# DSO_IO.net
KiCad netlist of a schematic drawn in Altium Designer
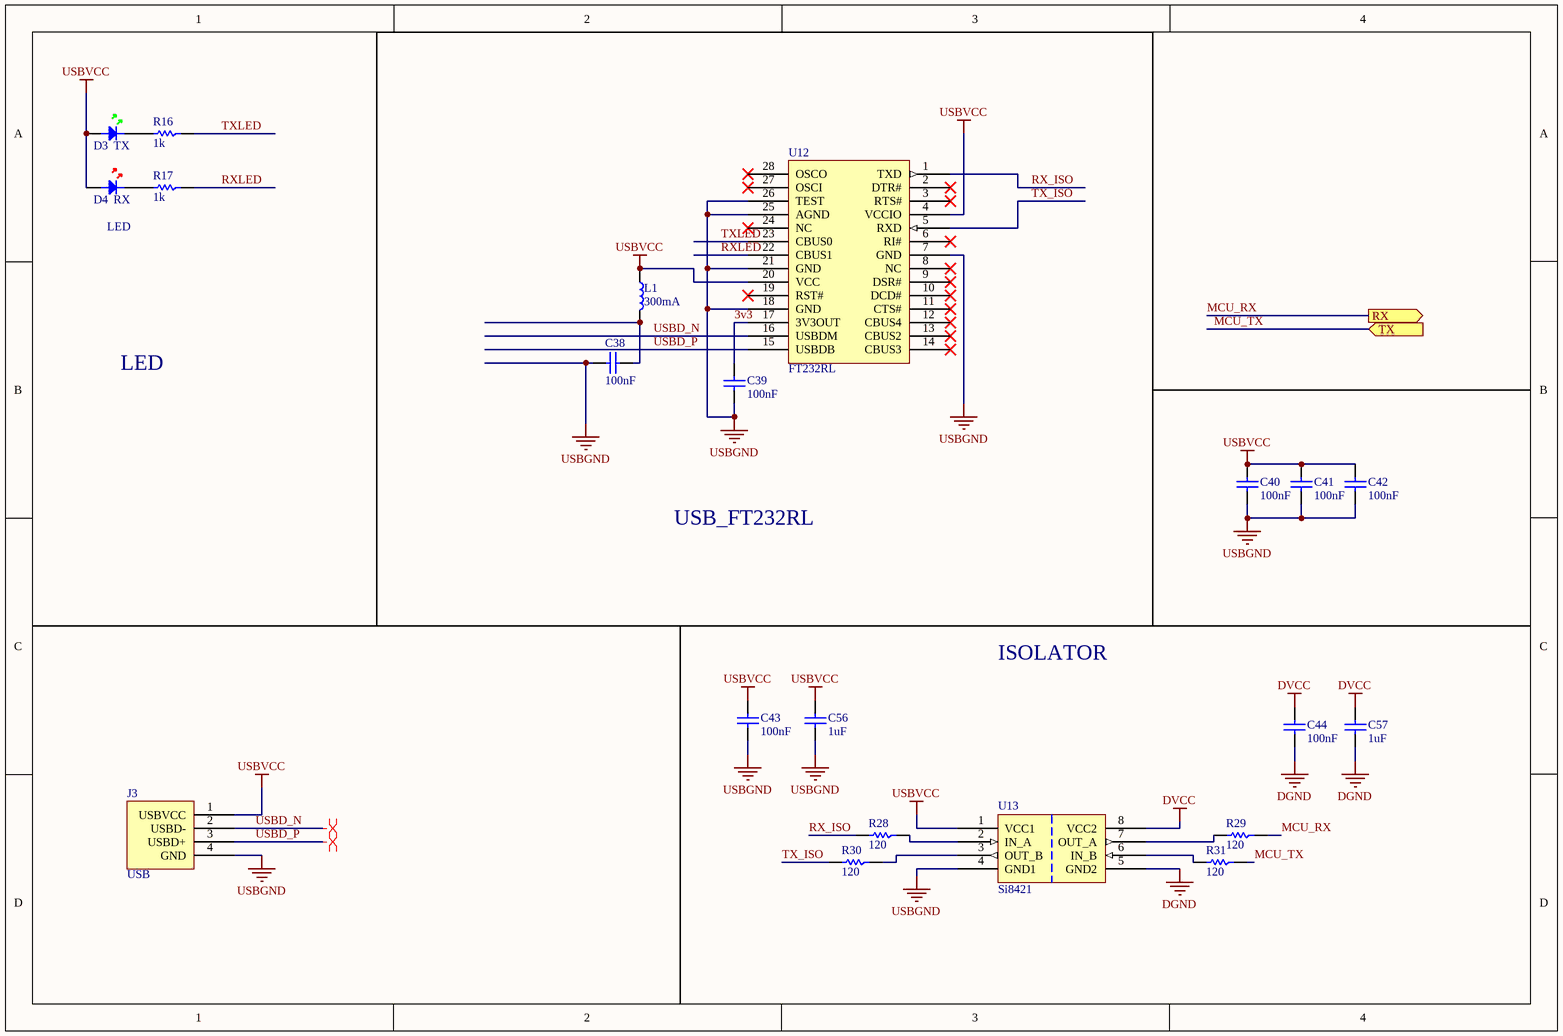
[diagram p0: DSO_IO.SchDoc]

(export (version "E")
  (design (tool "Eeschema 10.0.6"))
  (components
    (comp (ref "C38")
      (value "100nF")
      (footprint "0805C")
      (description "Capacitor")
      (fields (field (name "REVIEWED BY") "RM - 2018/08/05"))
      (libsource (lib "DSO") (part "C"))
    )
    (comp (ref "C39")
      (value "100nF")
      (footprint "0805C")
      (description "Capacitor")
      (fields (field (name "REVIEWED BY") "RM - 2018/08/05"))
      (libsource (lib "DSO") (part "C"))
    )
    (comp (ref "C40")
      (value "100nF")
      (footprint "0805C")
      (description "Capacitor")
      (fields (field (name "REVIEWED BY") "RM - 2018/08/05"))
      (libsource (lib "DSO") (part "C"))
    )
    (comp (ref "C41")
      (value "100nF")
      (footprint "0805C")
      (description "Capacitor")
      (fields (field (name "REVIEWED BY") "RM - 2018/08/05"))
      (libsource (lib "DSO") (part "C"))
    )
    (comp (ref "C42")
      (value "100nF")
      (footprint "0805C")
      (description "Capacitor")
      (fields (field (name "REVIEWED BY") "RM - 2018/08/05"))
      (libsource (lib "DSO") (part "C"))
    )
    (comp (ref "C43")
      (value "100nF")
      (footprint "0805C")
      (description "Capacitor")
      (fields (field (name "REVIEWED BY") "RM - 2018/08/05"))
      (libsource (lib "DSO") (part "C"))
    )
    (comp (ref "C44")
      (value "100nF")
      (footprint "0805C")
      (description "Capacitor")
      (fields (field (name "REVIEWED BY") "RM - 2018/08/05"))
      (libsource (lib "DSO") (part "C"))
    )
    (comp (ref "C56")
      (value "1uF")
      (footprint "0805C")
      (description "Capacitor")
      (fields (field (name "REVIEWED BY") "RM - 2018/08/05"))
      (libsource (lib "DSO") (part "C"))
    )
    (comp (ref "C57")
      (value "1uF")
      (footprint "0805C")
      (description "Capacitor")
      (fields (field (name "REVIEWED BY") "RM - 2018/08/05"))
      (libsource (lib "DSO") (part "C"))
    )
    (comp (ref "D3")
      (value "TX")
      (footprint "0805D-GREEN")
      (description "Light Emitting Diode")
      (fields (field (name "REVIEWED BY") "RM - 2018/08/05"))
      (libsource (lib "DSO") (part "LED GREEN"))
    )
    (comp (ref "D4")
      (value "RX")
      (footprint "0805D-RED")
      (description "Light Emitting Diode")
      (fields (field (name "REVIEWED BY") "RM - 2018/08/05"))
      (libsource (lib "DSO") (part "LED RED"))
    )
    (comp (ref "J3")
      (value "USB")
      (footprint "USBPLUG")
      (description "USB B Type Connector")
      (fields (field (name "REVIEWED BY") "RM - 2018/08/05"))
      (libsource (lib "DSO") (part "USBPLUG"))
    )
    (comp (ref "L1")
      (value "300mA")
      (footprint "0805")
      (description "Inductor")
      (fields (field (name "REVIEWED BY") "RM - 2018/08/05"))
      (libsource (lib "DSO") (part "I"))
    )
    (comp (ref "R16")
      (value "1k")
      (footprint "0805")
      (description "Resistor")
      (fields (field (name "REVIEWED BY") "RM - 2018/08/05"))
      (libsource (lib "DSO") (part "R"))
    )
    (comp (ref "R17")
      (value "1k")
      (footprint "0805")
      (description "Resistor")
      (fields (field (name "REVIEWED BY") "RM - 2018/08/05"))
      (libsource (lib "DSO") (part "R"))
    )
    (comp (ref "R28")
      (value "120")
      (footprint "0805")
      (description "Resistor")
      (fields (field (name "REVIEWED BY") "RM - 2018/08/05"))
      (libsource (lib "DSO") (part "R"))
    )
    (comp (ref "R29")
      (value "120")
      (footprint "0805")
      (description "Resistor")
      (fields (field (name "REVIEWED BY") "RM - 2018/08/05"))
      (libsource (lib "DSO") (part "R"))
    )
    (comp (ref "R30")
      (value "120")
      (footprint "0805")
      (description "Resistor")
      (fields (field (name "REVIEWED BY") "RM - 2018/08/05"))
      (libsource (lib "DSO") (part "R"))
    )
    (comp (ref "R31")
      (value "120")
      (footprint "0805")
      (description "Resistor")
      (fields (field (name "REVIEWED BY") "RM - 2018/08/05"))
      (libsource (lib "DSO") (part "R"))
    )
    (comp (ref "U12")
      (value "FT232RL")
      (footprint "SSOP-28")
      (description "USB to Serial bridge")
      (fields (field (name "REVIEWED BY") "RM - 2018/08/05"))
      (libsource (lib "DSO") (part "FT232RL"))
    )
    (comp (ref "U13")
      (value "Si8421")
      (footprint "SOIC-8")
      (description "Dual Channel Digital Isolator Both Ways")
      (fields (field (name "REVIEWED BY") "RM - 2018/08/05"))
      (libsource (lib "DSO") (part "Si8421"))
    )
  )
  (nets
    (net (code "1") (name "/3v3") (class "Default")
      (node (ref "C39") (pin "1") (pinfunction "1_1") (pintype "passive"))
      (node (ref "U12") (pin "17") (pinfunction "3V3OUT_17") (pintype "passive"))
    )
    (net (code "2") (name "/MCU_RX") (class "Default") (node (ref "R29") (pin "1") (pintype "passive")))
    (net (code "3") (name "/MCU_TX") (class "Default") (node (ref "R31") (pin "1") (pintype "passive")))
    (net (code "4") (name "/RXLED") (class "Default")
      (node (ref "R17") (pin "1") (pintype "passive"))
      (node (ref "U12") (pin "22") (pinfunction "CBUS1_22") (pintype "passive"))
    )
    (net (code "5") (name "/RX_ISO") (class "Default")
      (node (ref "R28") (pin "2") (pintype "passive"))
      (node (ref "U12") (pin "1") (pinfunction "TXD_1") (pintype "output"))
    )
    (net (code "6") (name "/TXLED") (class "Default")
      (node (ref "R16") (pin "1") (pintype "passive"))
      (node (ref "U12") (pin "23") (pinfunction "CBUS0_23") (pintype "passive"))
    )
    (net (code "7") (name "/TX_ISO") (class "Default")
      (node (ref "R30") (pin "2") (pintype "passive"))
      (node (ref "U12") (pin "5") (pinfunction "RXD_5") (pintype "input"))
    )
    (net (code "8") (name "/USBD_N") (class "Default")
      (node (ref "J3") (pin "2") (pinfunction "USBD-_2") (pintype "passive"))
      (node (ref "U12") (pin "16") (pinfunction "USBDM_16") (pintype "passive"))
    )
    (net (code "9") (name "/USBD_P") (class "Default")
      (node (ref "J3") (pin "3") (pinfunction "USBD+_3") (pintype "passive"))
      (node (ref "U12") (pin "15") (pinfunction "USBDB_15") (pintype "passive"))
    )
    (net (code "10") (name "DGND") (class "Default")
      (node (ref "C44") (pin "2") (pinfunction "2_2") (pintype "passive"))
      (node (ref "C57") (pin "2") (pinfunction "2_2") (pintype "passive"))
      (node (ref "U13") (pin "5") (pinfunction "GND2_5") (pintype "passive"))
    )
    (net (code "11") (name "DVCC") (class "Default")
      (node (ref "C44") (pin "1") (pinfunction "1_1") (pintype "passive"))
      (node (ref "C57") (pin "1") (pinfunction "1_1") (pintype "passive"))
      (node (ref "U13") (pin "8") (pinfunction "VCC2_8") (pintype "passive"))
    )
    (net (code "12") (name "Net-(C38-Pad1)") (class "Default")
      (node (ref "C38") (pin "1") (pinfunction "1_1") (pintype "passive"))
      (node (ref "L1") (pin "2") (pinfunction "2_2") (pintype "passive"))
    )
    (net (code "13") (name "Net-(D3-PadK)") (class "Default")
      (node (ref "D3") (pin "K") (pinfunction "K_K") (pintype "passive"))
      (node (ref "R16") (pin "2") (pintype "passive"))
    )
    (net (code "14") (name "Net-(D4-PadK)") (class "Default")
      (node (ref "D4") (pin "K") (pinfunction "K_K") (pintype "passive"))
      (node (ref "R17") (pin "2") (pintype "passive"))
    )
    (net (code "15") (name "Net-(U13-IN_A)") (class "Default")
      (node (ref "R28") (pin "1") (pintype "passive"))
      (node (ref "U13") (pin "2") (pinfunction "IN_A_2") (pintype "input"))
    )
    (net (code "16") (name "Net-(U13-IN_B)") (class "Default")
      (node (ref "R31") (pin "2") (pintype "passive"))
      (node (ref "U13") (pin "6") (pinfunction "IN_B_6") (pintype "input"))
    )
    (net (code "17") (name "Net-(U13-OUT_A)") (class "Default")
      (node (ref "R29") (pin "2") (pintype "passive"))
      (node (ref "U13") (pin "7") (pinfunction "OUT_A_7") (pintype "output"))
    )
    (net (code "18") (name "Net-(U13-OUT_B)") (class "Default")
      (node (ref "R30") (pin "1") (pintype "passive"))
      (node (ref "U13") (pin "3") (pinfunction "OUT_B_3") (pintype "output"))
    )
    (net (code "19") (name "USBGND") (class "Default")
      (node (ref "C38") (pin "2") (pinfunction "2_2") (pintype "passive"))
      (node (ref "C39") (pin "2") (pinfunction "2_2") (pintype "passive"))
      (node (ref "C40") (pin "2") (pinfunction "2_2") (pintype "passive"))
      (node (ref "C41") (pin "2") (pinfunction "2_2") (pintype "passive"))
      (node (ref "C42") (pin "2") (pinfunction "2_2") (pintype "passive"))
      (node (ref "C43") (pin "2") (pinfunction "2_2") (pintype "passive"))
      (node (ref "C56") (pin "2") (pinfunction "2_2") (pintype "passive"))
      (node (ref "J3") (pin "4") (pinfunction "GND_4") (pintype "passive"))
      (node (ref "U12") (pin "18") (pinfunction "GND_18") (pintype "passive"))
      (node (ref "U12") (pin "21") (pinfunction "GND_21") (pintype "passive"))
      (node (ref "U12") (pin "25") (pinfunction "AGND_25") (pintype "passive"))
      (node (ref "U12") (pin "26") (pinfunction "TEST_26") (pintype "passive"))
      (node (ref "U12") (pin "7") (pinfunction "GND_7") (pintype "passive"))
      (node (ref "U13") (pin "4") (pinfunction "GND1_4") (pintype "passive"))
    )
    (net (code "20") (name "USBVCC") (class "Default")
      (node (ref "C40") (pin "1") (pinfunction "1_1") (pintype "passive"))
      (node (ref "C41") (pin "1") (pinfunction "1_1") (pintype "passive"))
      (node (ref "C42") (pin "1") (pinfunction "1_1") (pintype "passive"))
      (node (ref "C43") (pin "1") (pinfunction "1_1") (pintype "passive"))
      (node (ref "C56") (pin "1") (pinfunction "1_1") (pintype "passive"))
      (node (ref "D3") (pin "A") (pinfunction "A_A") (pintype "passive"))
      (node (ref "D4") (pin "A") (pinfunction "A_A") (pintype "passive"))
      (node (ref "J3") (pin "1") (pinfunction "USBVCC_1") (pintype "passive"))
      (node (ref "L1") (pin "1") (pinfunction "1_1") (pintype "passive"))
      (node (ref "U12") (pin "20") (pinfunction "VCC_20") (pintype "passive"))
      (node (ref "U12") (pin "4") (pinfunction "VCCIO_4") (pintype "passive"))
      (node (ref "U13") (pin "1") (pinfunction "VCC1_1") (pintype "passive"))
    )
    (net (code "21") (name "unconnected-(U12-CBUS2-Pad13)") (class "Default")
      (node (ref "U12") (pin "13") (pinfunction "CBUS2_13") (pintype "passive+no_connect"))
    )
    (net (code "22") (name "unconnected-(U12-CBUS3-Pad14)") (class "Default")
      (node (ref "U12") (pin "14") (pinfunction "CBUS3_14") (pintype "passive+no_connect"))
    )
    (net (code "23") (name "unconnected-(U12-CBUS4-Pad12)") (class "Default")
      (node (ref "U12") (pin "12") (pinfunction "CBUS4_12") (pintype "passive+no_connect"))
    )
    (net (code "24") (name "unconnected-(U12-CTS#-Pad11)") (class "Default")
      (node (ref "U12") (pin "11") (pinfunction "CTS#_11") (pintype "passive+no_connect"))
    )
    (net (code "25") (name "unconnected-(U12-DCD#-Pad10)") (class "Default")
      (node (ref "U12") (pin "10") (pinfunction "DCD#_10") (pintype "passive+no_connect"))
    )
    (net (code "26") (name "unconnected-(U12-DSR#-Pad9)") (class "Default")
      (node (ref "U12") (pin "9") (pinfunction "DSR#_9") (pintype "passive+no_connect"))
    )
    (net (code "27") (name "unconnected-(U12-DTR#-Pad2)") (class "Default")
      (node (ref "U12") (pin "2") (pinfunction "DTR#_2") (pintype "passive+no_connect"))
    )
    (net (code "28") (name "unconnected-(U12-NC-Pad8)") (class "Default")
      (node (ref "U12") (pin "8") (pinfunction "NC_8") (pintype "passive+no_connect"))
    )
    (net (code "29") (name "unconnected-(U12-NC-Pad24)") (class "Default")
      (node (ref "U12") (pin "24") (pinfunction "NC_24") (pintype "passive+no_connect"))
    )
    (net (code "30") (name "unconnected-(U12-OSCI-Pad27)") (class "Default")
      (node (ref "U12") (pin "27") (pinfunction "OSCI_27") (pintype "passive+no_connect"))
    )
    (net (code "31") (name "unconnected-(U12-OSCO-Pad28)") (class "Default")
      (node (ref "U12") (pin "28") (pinfunction "OSCO_28") (pintype "passive+no_connect"))
    )
    (net (code "32") (name "unconnected-(U12-RI#-Pad6)") (class "Default")
      (node (ref "U12") (pin "6") (pinfunction "RI#_6") (pintype "passive+no_connect"))
    )
    (net (code "33") (name "unconnected-(U12-RST#-Pad19)") (class "Default")
      (node (ref "U12") (pin "19") (pinfunction "RST#_19") (pintype "passive+no_connect"))
    )
    (net (code "34") (name "unconnected-(U12-RTS#-Pad3)") (class "Default")
      (node (ref "U12") (pin "3") (pinfunction "RTS#_3") (pintype "passive+no_connect"))
    )
  )
)
